# Sheet1.net
KiCad netlist of a schematic drawn in Altium Designer
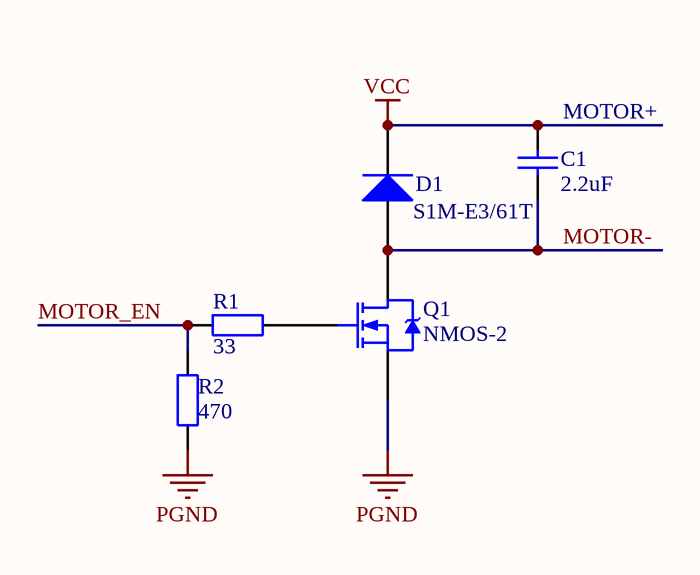
[diagram p0: Sheet1.SchDoc]

(export (version "E")
  (design (tool "Eeschema 10.0.6"))
  (components
    (comp (ref "C1")
      (value "2.2uF")
      (footprint "0805[cap]")
      (description "Chip Capacitor")
      (fields (field (name "Comment") "CT41L-0805-2C1-25V-225K"))
      (libsource (lib "passive") (part "Capacitor"))
    )
    (comp (ref "D1")
      (value "S1M-E3/61T")
      (footprint "M7")
      (description "1 Amp General Purpose Rectifier")
      (libsource (lib "Miscellaneous Devices") (part "Diode 1N4007"))
    )
    (comp (ref "Q1")
      (value "NMOS-2")
      (footprint "DPAK228P991X239-3N")
      (description "N-Channel Power MOSFET")
      (fields (field (name "PUBLISHER") "Altium Limited"))
      (libsource (lib "Miscellaneous Devices") (part "NMOS-2"))
    )
    (comp (ref "R1")
      (value "33")
      (footprint "0603[res]")
      (description "Resistor")
      (fields (field (name "Comment") "RMK1608MB102J"))
      (libsource (lib "") (part "Resistor_1"))
    )
    (comp (ref "R2")
      (value "470")
      (footprint "0603[res]")
      (description "Resistor")
      (fields (field (name "Comment") "RMK1608MB102J"))
      (libsource (lib "passive") (part "Resistor"))
    )
  )
  (nets
    (net (code "1") (name "/MOTOR-") (class "Default")
      (node (ref "C1") (pin "1") (pinfunction "1_1") (pintype "passive"))
      (node (ref "D1") (pin "1") (pinfunction "A_1") (pintype "passive"))
      (node (ref "Q1") (pin "2") (pinfunction "D_2") (pintype "passive"))
    )
    (net (code "2") (name "/MOTOR_EN") (class "Default")
      (node (ref "R1") (pin "1") (pinfunction "1_1") (pintype "passive"))
      (node (ref "R2") (pin "2") (pinfunction "2_2") (pintype "passive"))
    )
    (net (code "3") (name "Net-(Q1-G)") (class "Default")
      (node (ref "Q1") (pin "1") (pinfunction "G_1") (pintype "passive"))
      (node (ref "R1") (pin "2") (pinfunction "2_2") (pintype "passive"))
    )
    (net (code "4") (name "PGND") (class "Default")
      (node (ref "Q1") (pin "3") (pinfunction "S_3") (pintype "passive"))
      (node (ref "R2") (pin "1") (pinfunction "1_1") (pintype "passive"))
    )
    (net (code "5") (name "VCC") (class "Default")
      (node (ref "C1") (pin "2") (pinfunction "2_2") (pintype "passive"))
      (node (ref "D1") (pin "2") (pinfunction "K_2") (pintype "passive"))
    )
  )
)
